# Power_SCH.net
KiCad netlist of a schematic drawn in Altium Designer
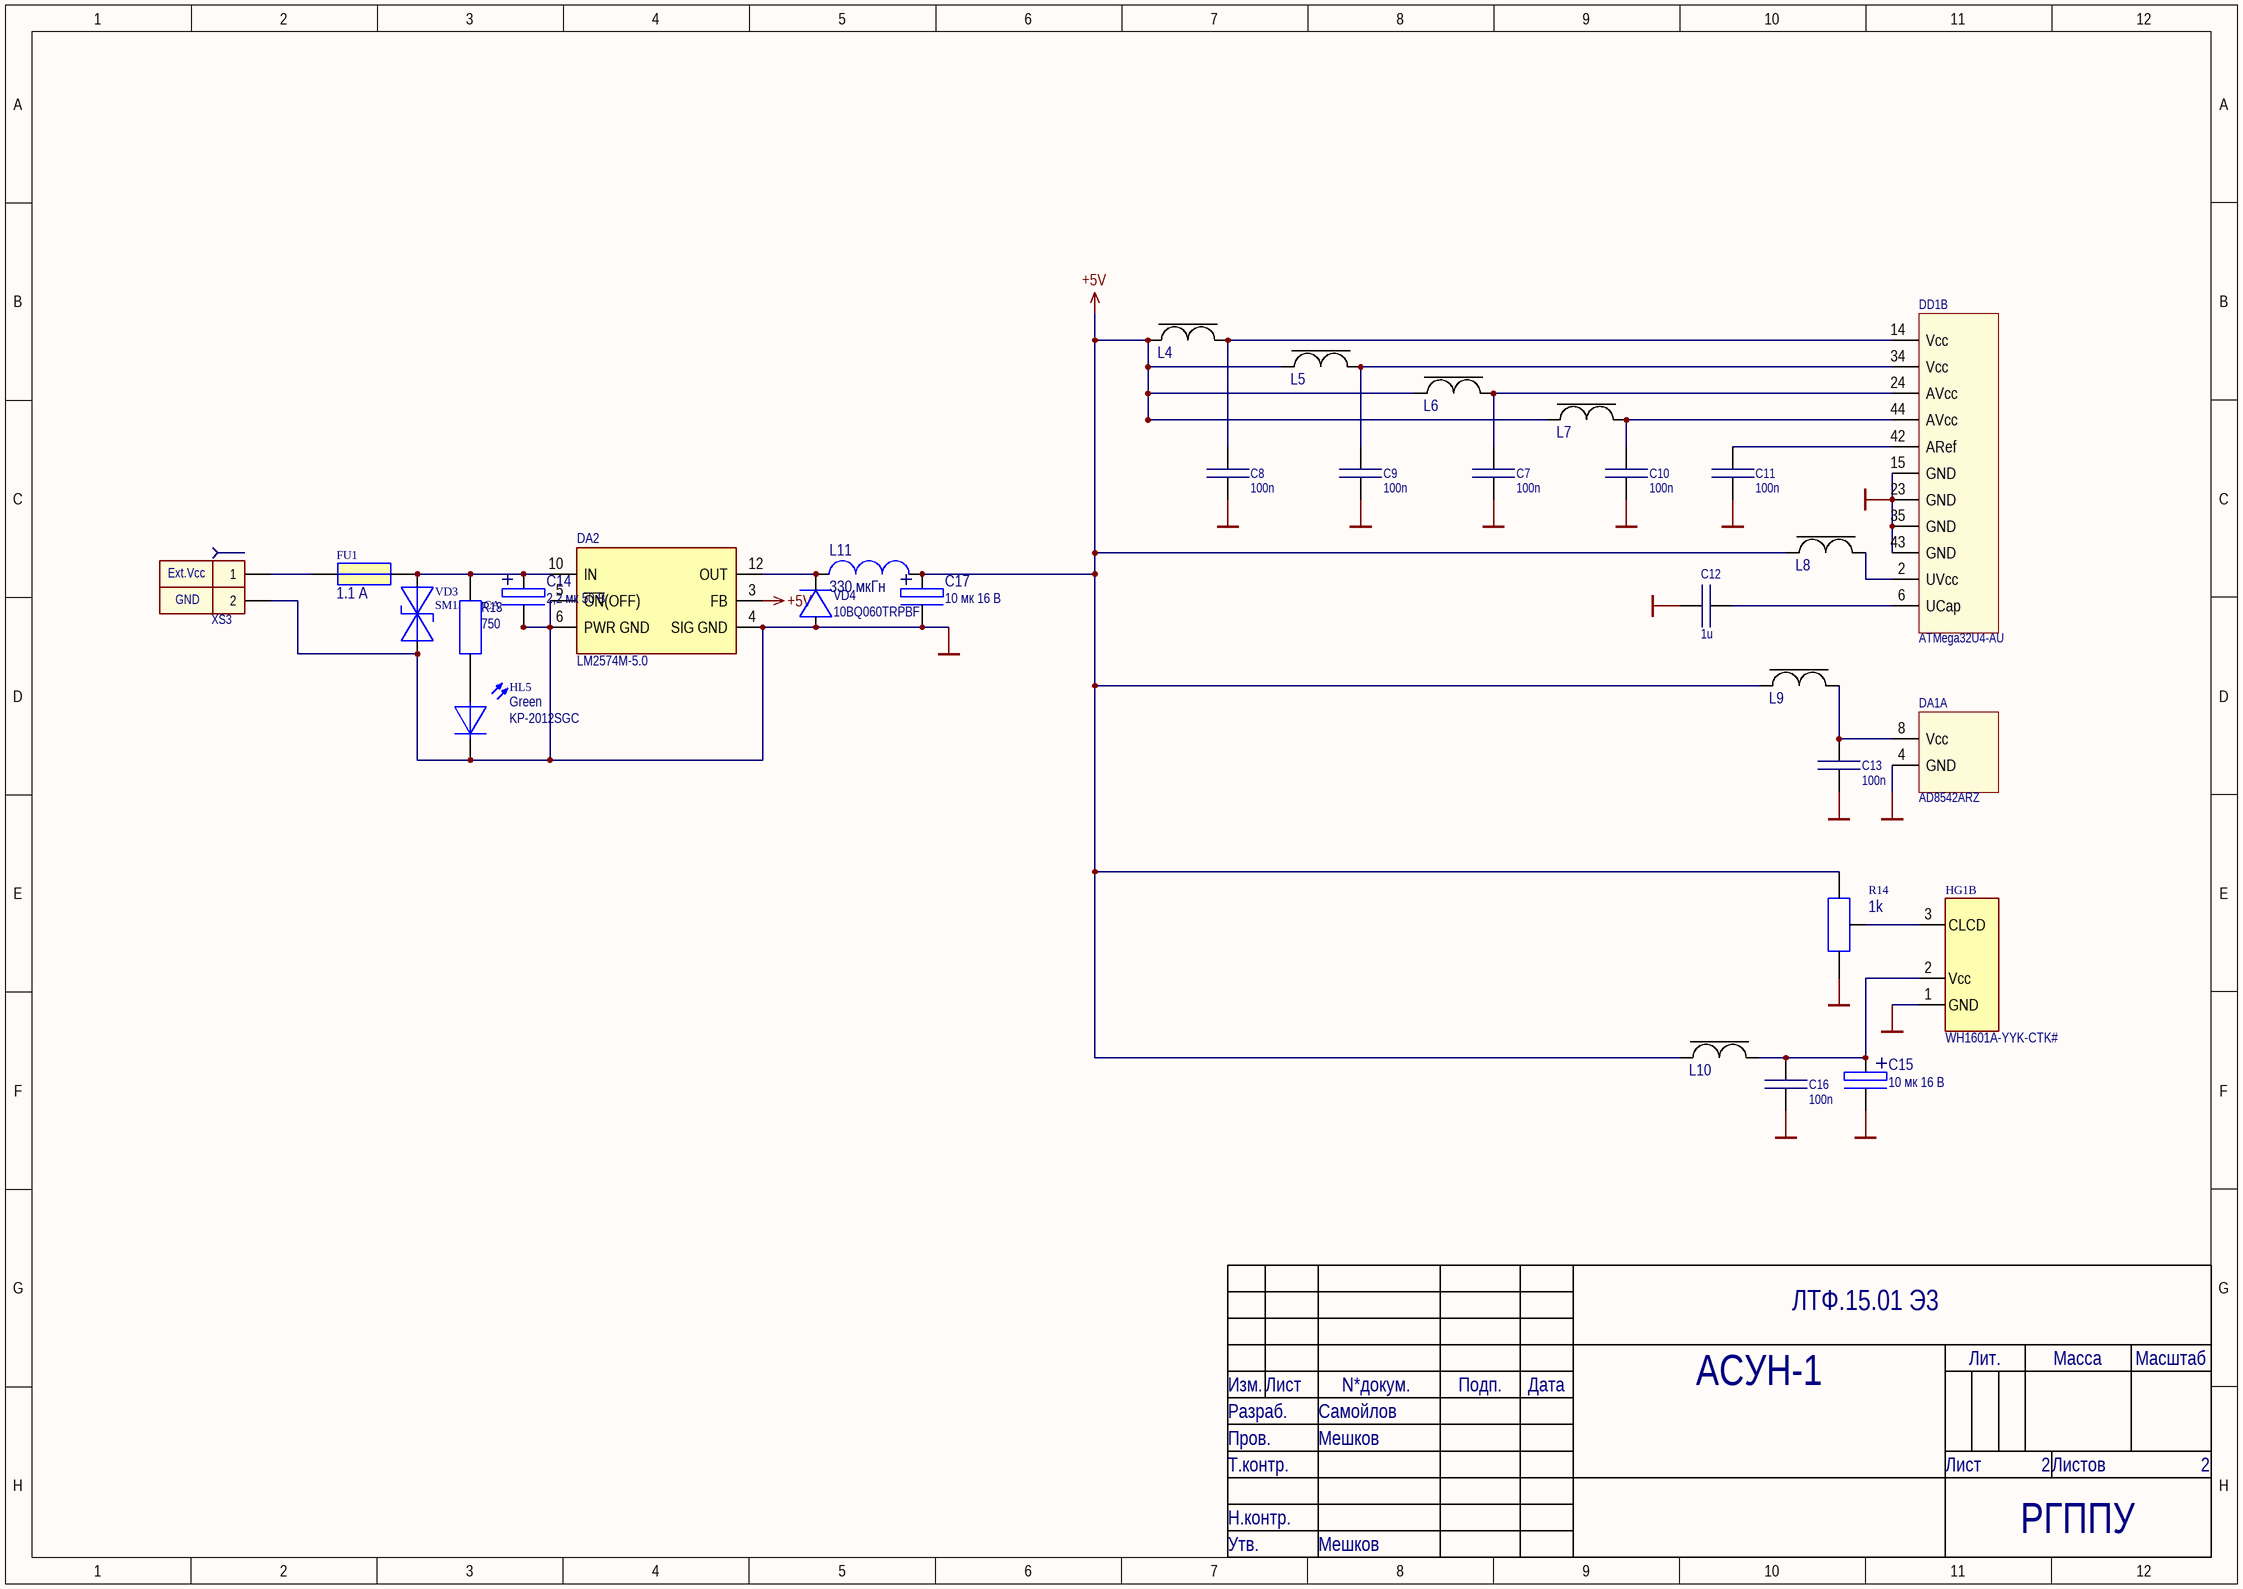
[diagram p0: Power_SCH.SchDoc]

(export (version "E")
  (design (tool "Eeschema 10.0.6"))
  (components
    (comp (ref "C7")
      (value "100n")
      (footprint "SMDRC0805")
      (description "Generic capasitor non-polar")
      (fields (field (name "PARTNUMBER") "Capacitor 0805 100n"))
      (libsource (lib "library") (part "Capacitor"))
    )
    (comp (ref "C8")
      (value "100n")
      (footprint "SMDRC0805")
      (description "Generic capasitor non-polar")
      (fields (field (name "PARTNUMBER") "Capacitor 0805 100n"))
      (libsource (lib "library") (part "Capacitor"))
    )
    (comp (ref "C9")
      (value "100n")
      (footprint "SMDRC0805")
      (description "Generic capasitor non-polar")
      (fields (field (name "PARTNUMBER") "Capacitor 0805 100n"))
      (libsource (lib "library") (part "Capacitor"))
    )
    (comp (ref "C10")
      (value "100n")
      (footprint "SMDRC0805")
      (description "Generic capasitor non-polar")
      (fields (field (name "PARTNUMBER") "Capacitor 0805 100n"))
      (libsource (lib "library") (part "Capacitor"))
    )
    (comp (ref "C11")
      (value "100n")
      (footprint "SMDRC0805")
      (description "Generic capasitor non-polar")
      (fields (field (name "PARTNUMBER") "Capacitor 0805 100n"))
      (libsource (lib "library") (part "Capacitor"))
    )
    (comp (ref "C12")
      (value "1u")
      (footprint "SMDRC0805")
      (description "Generic capasitor non-polar")
      (fields (field (name "PARTNUMBER") "Capacitor 0805 1u"))
      (libsource (lib "library") (part "Capacitor"))
    )
    (comp (ref "C13")
      (value "100n")
      (footprint "SMDRC0805")
      (description "Generic capasitor non-polar")
      (fields (field (name "PARTNUMBER") "Capacitor 0805 100n"))
      (libsource (lib "library") (part "Capacitor"))
    )
    (comp (ref "C14")
      (value "2,2 мк 50 В")
      (footprint "Cap:CAP_POLAR_ELLYTE_B")
      (description "2,2uF 50V Polar capacitor")
      (fields
        (field (name "MANUFACTURERPARTNUMBER") "CA050M2R20REB-0405")
        (field (name "MANUFACTURER") "Yageo")
      )
      (libsource (lib "Cap") (part "02200_050"))
    )
    (comp (ref "C15")
      (value "10 мк 16 В")
      (footprint "Cap:CAP_POLAR_ELLYTE_B")
      (description "10uF 16V Polar SMD cap")
      (fields
        (field (name "MANUFACTURERPARTNUMBER") "CA016M0010REB-0405")
        (field (name "MANUFACTURER") "YAGEO")
      )
      (libsource (lib "Cap") (part "10000_016"))
    )
    (comp (ref "C16")
      (value "100n")
      (footprint "SMDRC0805")
      (description "Generic capasitor non-polar")
      (fields (field (name "PARTNUMBER") "Capacitor 0805 100n"))
      (libsource (lib "library") (part "Capacitor"))
    )
    (comp (ref "C17")
      (value "10 мк 16 В")
      (footprint "Cap:CAP_POLAR_ELLYTE_B")
      (description "10uF 16V Polar SMD cap")
      (fields
        (field (name "MANUFACTURERPARTNUMBER") "CA016M0010REB-0405")
        (field (name "MANUFACTURER") "YAGEO")
      )
      (libsource (lib "Cap") (part "10000_016"))
    )
    (comp (ref "DA1")
      (value "AD8542ARZ")
      (footprint "Op_amp:AD8542ARZ")
      (libsource (lib "Op_amp") (part "AD8542ARZ"))
    )
    (comp (ref "DA2")
      (value "LM2574M-5.0")
      (footprint "Power:SOIC127P1030X264-14M")
      (fields (field (name "MANUFACTURERPARTNUMBER") "LM2574M-5.0"))
      (libsource (lib "Power") (part "LM2574M-5.0"))
    )
    (comp (ref "DD1")
      (value "ATMega32U4-AU")
      (footprint "Atmel Microcontroller 8-Bit Automotive AVR:44ML_L")
      (libsource (lib "Microcontrollers") (part "ATMega32U4"))
    )
    (comp (ref "FU1")
      (value "1.1 А")
      (footprint "Power:EFuse 1.1A")
      (description "Fuse")
      (fields (field (name "MANUFACTURERPARTNUMBER") "EFuse LP60-110F"))
      (libsource (lib "Power") (part "EFuse LP60-110F"))
    )
    (comp (ref "HG1")
      (value "WH1601A-YYK-CTK#")
      (footprint "Indicator:WH1601A")
      (description "Liquid crystal display")
      (fields
        (field (name "MANUFACTURER") "Winstar")
        (field (name "MANUFACTURERPARTNUMBER") "WH1601A-YYK-CTK#")
      )
      (libsource (lib "Indicator") (part "LCD 1601A"))
    )
    (comp (ref "HL5")
      (value "Green")
      (footprint "Indicator:DIOMELF2012M")
      (description "Diod LED SMD Green")
      (fields (field (name "MANUFACTURERPARTNUMBER") "KP-2012SGC"))
      (libsource (lib "Indicator") (part "LED1_G"))
    )
    (comp (ref "L4")
      (value "MPZ1608S181A")
      (footprint "Inductor:INDC0603X03M")
      (description "Ferrite Bead")
      (libsource (lib "") (part "Ferrite Bead_1"))
    )
    (comp (ref "L5")
      (value "MPZ1608S181A")
      (footprint "Inductor:INDC0603X03M")
      (description "Ferrite Bead")
      (libsource (lib "") (part "Ferrite Bead_1"))
    )
    (comp (ref "L6")
      (value "MPZ1608S181A")
      (footprint "Inductor:INDC0603X03M")
      (description "Ferrite Bead")
      (libsource (lib "") (part "Ferrite Bead_1"))
    )
    (comp (ref "L7")
      (value "MPZ1608S181A")
      (footprint "Inductor:INDC0603X03M")
      (description "Ferrite Bead")
      (libsource (lib "") (part "Ferrite Bead_1"))
    )
    (comp (ref "L8")
      (value "MPZ1608S181A")
      (footprint "Inductor:INDC0603X03M")
      (description "Ferrite Bead")
      (libsource (lib "") (part "Ferrite Bead_1"))
    )
    (comp (ref "L9")
      (value "MPZ1608S181A")
      (footprint "Inductor:INDC0603X03M")
      (description "Ferrite Bead")
      (libsource (lib "Inductor") (part "Ferrite Bead"))
    )
    (comp (ref "L10")
      (value "MPZ1608S181A")
      (footprint "Inductor:INDC0603X03M")
      (description "Ferrite Bead")
      (libsource (lib "") (part "Ferrite Bead_1"))
    )
    (comp (ref "L11")
      (value "330 мкГн")
      (footprint "Inductor:INDP7972X50M")
      (description "Inductor")
      (fields (field (name "MANUFACTURERPARTNUMBER") "SCD0705T-331K-N"))
      (libsource (lib "Inductor") (part "SCD0705T-331K-N"))
    )
    (comp (ref "R13")
      (value "750")
      (footprint "SMDRC0805")
      (description "Generic resistor")
      (fields (field (name "PARTNUMBER") "Resistor 0805 750"))
      (libsource (lib "library") (part "Resistor"))
    )
    (comp (ref "R14")
      (value "1k")
      (footprint "Resistor:T93YA")
      (description "Resistor trimming")
      (fields (field (name "MANUFACTURERPARTNUMBER") "T93YA102KT20") (field (name "MANUFACTURER") "VISHAY"))
      (libsource (lib "Resistor") (part "Res trim_1k"))
    )
    (comp (ref "VD3")
      (value "SM15T12CA")
      (footprint "DIod:SUPRES3216X18N")
      (description "Diod suppressor")
      (fields
        (field (name "MANUFACTURER") "ST Microelectronics")
        (field (name "MANUFACTURERPARTNUMBER") "SM15T12CA")
      )
      (libsource (lib "Diod") (part "SM15T12CA"))
    )
    (comp (ref "VD4")
      (value "10BQ060TRPBF")
      (footprint "DIod:SHOTKY 4.1x3.3")
      (description "DIODE SCHOTTKY 60V 1A DO214AA")
      (fields
        (field (name "MANUFACTURER") "Vishay Semiconductor Diodes Division")
        (field (name "MANUFACTURERPARTNUMBER") "10BQ060TRPBF")
      )
      (libsource (lib "Diod") (part "10BQ060TRPBF"))
    )
    (comp (ref "XS3")
      (value "330-031-12")
      (footprint "Connector:330-031-12")
      (libsource (lib "Connector") (part "330-031-12"))
    )
  )
  (nets
    (net (code "1") (name "+5V") (class "Default")
      (node (ref "C17") (pin "2") (pinfunction "+_2") (pintype "passive"))
      (node (ref "DA2") (pin "3") (pinfunction "FB_3") (pintype "passive"))
      (node (ref "L10") (pin "2") (pinfunction "2_2") (pintype "passive"))
      (node (ref "L11") (pin "1") (pinfunction "1_1") (pintype "passive"))
      (node (ref "L4") (pin "2") (pinfunction "2_2") (pintype "passive"))
      (node (ref "L5") (pin "2") (pinfunction "2_2") (pintype "passive"))
      (node (ref "L6") (pin "2") (pinfunction "2_2") (pintype "passive"))
      (node (ref "L7") (pin "2") (pinfunction "2_2") (pintype "passive"))
      (node (ref "L8") (pin "2") (pinfunction "2_2") (pintype "passive"))
      (node (ref "L9") (pin "1") (pinfunction "1_1") (pintype "passive"))
      (node (ref "R14") (pin "3") (pinfunction "3_3") (pintype "passive"))
    )
    (net (code "2") (name "GND") (class "Default")
      (node (ref "C10") (pin "2") (pintype "passive"))
      (node (ref "C11") (pin "1") (pintype "passive"))
      (node (ref "C12") (pin "2") (pintype "passive"))
      (node (ref "C13") (pin "2") (pintype "passive"))
      (node (ref "C14") (pin "1") (pinfunction "-_1") (pintype "passive"))
      (node (ref "C15") (pin "1") (pinfunction "-_1") (pintype "passive"))
      (node (ref "C16") (pin "2") (pintype "passive"))
      (node (ref "C17") (pin "1") (pinfunction "-_1") (pintype "passive"))
      (node (ref "C7") (pin "2") (pintype "passive"))
      (node (ref "C8") (pin "2") (pintype "passive"))
      (node (ref "C9") (pin "2") (pintype "passive"))
      (node (ref "DA1") (pin "4") (pinfunction "GND_4") (pintype "passive"))
      (node (ref "DA2") (pin "4") (pinfunction "SIG_GND_4") (pintype "passive"))
      (node (ref "DA2") (pin "5") (pinfunction "~{ON}(OFF)_5") (pintype "passive"))
      (node (ref "DA2") (pin "6") (pinfunction "PWR_GND_6") (pintype "passive"))
      (node (ref "DD1") (pin "15") (pinfunction "GND_15") (pintype "passive"))
      (node (ref "DD1") (pin "23") (pinfunction "GND_23") (pintype "passive"))
      (node (ref "DD1") (pin "35") (pinfunction "GND_35") (pintype "passive"))
      (node (ref "DD1") (pin "43") (pinfunction "GND_43") (pintype "passive"))
      (node (ref "HG1") (pin "1") (pinfunction "GND_1") (pintype "power_in"))
      (node (ref "HL5") (pin "2") (pinfunction "2_2") (pintype "passive"))
      (node (ref "R14") (pin "1") (pinfunction "1_1") (pintype "passive"))
      (node (ref "VD3") (pin "1") (pinfunction "1_1") (pintype "passive"))
      (node (ref "VD4") (pin "A") (pinfunction "A_A") (pintype "passive"))
      (node (ref "XS3") (pin "2") (pinfunction "2_2") (pintype "passive"))
    )
    (net (code "3") (name "Net-(C7-Pad1)") (class "Default")
      (node (ref "C7") (pin "1") (pintype "passive"))
      (node (ref "DD1") (pin "24") (pinfunction "AVсс_24") (pintype "passive"))
      (node (ref "L6") (pin "1") (pinfunction "1_1") (pintype "passive"))
    )
    (net (code "4") (name "Net-(C8-Pad1)") (class "Default")
      (node (ref "C8") (pin "1") (pintype "passive"))
      (node (ref "DD1") (pin "14") (pinfunction "Vсс_14") (pintype "passive"))
      (node (ref "L4") (pin "1") (pinfunction "1_1") (pintype "passive"))
    )
    (net (code "5") (name "Net-(C9-Pad1)") (class "Default")
      (node (ref "C9") (pin "1") (pintype "passive"))
      (node (ref "DD1") (pin "34") (pinfunction "Vсс_34") (pintype "passive"))
      (node (ref "L5") (pin "1") (pinfunction "1_1") (pintype "passive"))
    )
    (net (code "6") (name "Net-(C10-Pad1)") (class "Default")
      (node (ref "C10") (pin "1") (pintype "passive"))
      (node (ref "DD1") (pin "44") (pinfunction "AVсс_44") (pintype "passive"))
      (node (ref "L7") (pin "1") (pinfunction "1_1") (pintype "passive"))
    )
    (net (code "7") (name "Net-(C14-+)") (class "Default")
      (node (ref "C14") (pin "2") (pinfunction "+_2") (pintype "passive"))
      (node (ref "DA2") (pin "10") (pinfunction "IN_10") (pintype "passive"))
      (node (ref "FU1") (pin "2") (pinfunction "2_2") (pintype "passive"))
      (node (ref "R13") (pin "2") (pinfunction "2_2") (pintype "passive"))
      (node (ref "VD3") (pin "2") (pinfunction "2_2") (pintype "passive"))
    )
    (net (code "8") (name "Net-(C15-+)") (class "Default")
      (node (ref "C15") (pin "2") (pinfunction "+_2") (pintype "passive"))
      (node (ref "C16") (pin "1") (pintype "passive"))
      (node (ref "HG1") (pin "2") (pinfunction "Vcc_2") (pintype "power_in"))
      (node (ref "L10") (pin "1") (pinfunction "1_1") (pintype "passive"))
    )
    (net (code "9") (name "Net-(DA1A-Vcc)") (class "Default")
      (node (ref "C13") (pin "1") (pintype "passive"))
      (node (ref "DA1") (pin "8") (pinfunction "Vcc_8") (pintype "passive"))
      (node (ref "L9") (pin "2") (pinfunction "2_2") (pintype "passive"))
    )
    (net (code "10") (name "Net-(DA2-OUT)") (class "Default")
      (node (ref "DA2") (pin "12") (pinfunction "OUT_12") (pintype "passive"))
      (node (ref "L11") (pin "2") (pinfunction "2_2") (pintype "passive"))
      (node (ref "VD4") (pin "K") (pinfunction "K_K") (pintype "passive"))
    )
    (net (code "11") (name "Net-(DD1B-ARef)") (class "Default")
      (node (ref "C11") (pin "2") (pintype "passive"))
      (node (ref "DD1") (pin "42") (pinfunction "ARef_42") (pintype "passive"))
    )
    (net (code "12") (name "Net-(DD1B-UCap)") (class "Default")
      (node (ref "C12") (pin "1") (pintype "passive"))
      (node (ref "DD1") (pin "6") (pinfunction "UCap_6") (pintype "passive"))
    )
    (net (code "13") (name "Net-(DD1B-UVcc)") (class "Default")
      (node (ref "DD1") (pin "2") (pinfunction "UVcc_2") (pintype "passive"))
      (node (ref "L8") (pin "1") (pinfunction "1_1") (pintype "passive"))
    )
    (net (code "14") (name "Net-(FU1-Pad1)") (class "Default")
      (node (ref "FU1") (pin "1") (pinfunction "1_1") (pintype "passive"))
      (node (ref "XS3") (pin "1") (pinfunction "1_1") (pintype "passive"))
    )
    (net (code "15") (name "Net-(HG1B-CLCD)") (class "Default")
      (node (ref "HG1") (pin "3") (pinfunction "CLCD_3") (pintype "power_in"))
      (node (ref "R14") (pin "2") (pinfunction "2_2") (pintype "passive"))
    )
    (net (code "16") (name "Net-(HL5-Pad1)") (class "Default")
      (node (ref "HL5") (pin "1") (pinfunction "1_1") (pintype "passive"))
      (node (ref "R13") (pin "1") (pinfunction "1_1") (pintype "passive"))
    )
  )
)
